# IR_Sensor.net
KiCad netlist of a schematic drawn in EAGLE
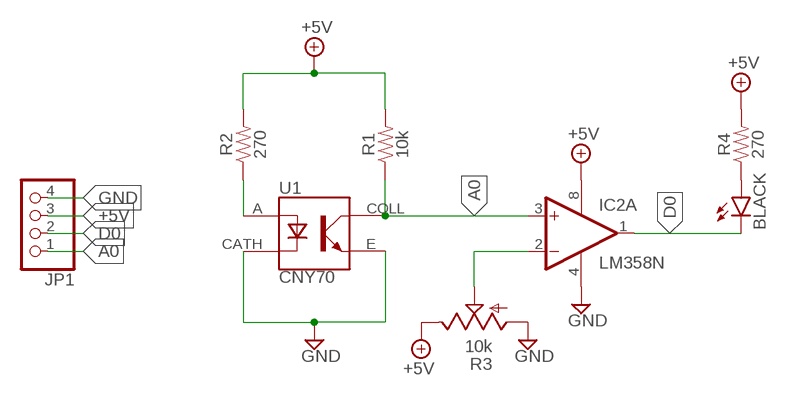
[diagram p0: schematic, sheet 1]

(export (version "E")
  (design (tool "Eeschema 10.0.6"))
  (components
    (comp (ref "BLACK")
      (value "LED3MM")
      (footprint "eagle-import:LED3MM")
      (libsource (lib "eagle-import") (part "LED3MM"))
    )
    (comp (ref "IC2")
      (value "LM358N")
      (footprint "eagle-import:DIL08")
      (libsource (lib "eagle-import") (part "LM358N"))
    )
    (comp (ref "JP1")
      (value "PINHD-1X4/90")
      (footprint "eagle-import:1X04_90")
      (libsource (lib "eagle-import") (part "PINHD-1X4/90"))
    )
    (comp (ref "R1")
      (value "10k")
      (footprint "eagle-import:AXIAL-0.3")
      (libsource (lib "eagle-import") (part "RESISTORAXIAL-0.3"))
    )
    (comp (ref "R2")
      (value "270")
      (footprint "eagle-import:AXIAL-0.3")
      (libsource (lib "eagle-import") (part "RESISTORAXIAL-0.3"))
    )
    (comp (ref "R3")
      (value "10k")
      (footprint "eagle-import:CA6V")
      (libsource (lib "eagle-import") (part "TRIM_US-CA6V"))
    )
    (comp (ref "R4")
      (value "270")
      (footprint "eagle-import:AXIAL-0.3")
      (libsource (lib "eagle-import") (part "RESISTORAXIAL-0.3"))
    )
    (comp (ref "U1")
      (value "CNY70")
      (footprint "eagle-import:DIPS254W50P254L710H600Q4")
      (fields (field (name "MF") "Vishay"))
      (libsource (lib "eagle-import") (part "CNY70"))
    )
  )
  (nets
    (net (code "1") (name "+5V") (class "Default")
      (node (ref "IC2") (pin "8") (pinfunction "V+_8") (pintype "power_in"))
      (node (ref "JP1") (pin "3") (pinfunction "3_3") (pintype "passive"))
      (node (ref "R1") (pin "P$2") (pinfunction "2_P$2") (pintype "passive"))
      (node (ref "R2") (pin "P$2") (pinfunction "2_P$2") (pintype "passive"))
      (node (ref "R3") (pin "E") (pinfunction "E_E") (pintype "passive"))
      (node (ref "R4") (pin "P$2") (pinfunction "2_P$2") (pintype "passive"))
    )
    (net (code "2") (name "A0") (class "Default")
      (node (ref "IC2") (pin "3") (pinfunction "+IN_3") (pintype "input"))
      (node (ref "JP1") (pin "1") (pinfunction "1_1") (pintype "passive"))
      (node (ref "R1") (pin "P$1") (pinfunction "1_P$1") (pintype "passive"))
      (node (ref "U1") (pin "COLL") (pinfunction "COLL_COLL") (pintype "passive"))
    )
    (net (code "3") (name "D0") (class "Default")
      (node (ref "BLACK") (pin "K") (pinfunction "C_K") (pintype "passive"))
      (node (ref "IC2") (pin "1") (pinfunction "OUT_1") (pintype "output"))
      (node (ref "JP1") (pin "2") (pinfunction "2_2") (pintype "passive"))
    )
    (net (code "4") (name "GND") (class "Default")
      (node (ref "IC2") (pin "4") (pinfunction "V-_4") (pintype "power_in"))
      (node (ref "JP1") (pin "4") (pinfunction "4_4") (pintype "passive"))
      (node (ref "R3") (pin "A") (pinfunction "A_A") (pintype "passive"))
      (node (ref "U1") (pin "CATH") (pinfunction "CATH_CATH") (pintype "passive"))
      (node (ref "U1") (pin "E") (pinfunction "E_E") (pintype "passive"))
    )
    (net (code "5") (name "Net-(IC2A--IN)") (class "Default")
      (node (ref "IC2") (pin "2") (pinfunction "-IN_2") (pintype "input"))
      (node (ref "R3") (pin "S") (pinfunction "S_S") (pintype "passive"))
    )
    (net (code "6") (name "Net-(R2-1)") (class "Default")
      (node (ref "R2") (pin "P$1") (pinfunction "1_P$1") (pintype "passive"))
      (node (ref "U1") (pin "A") (pinfunction "A_A") (pintype "passive"))
    )
    (net (code "7") (name "Net-(R4-1)") (class "Default")
      (node (ref "BLACK") (pin "A") (pinfunction "A_A") (pintype "passive"))
      (node (ref "R4") (pin "P$1") (pinfunction "1_P$1") (pintype "passive"))
    )
  )
)
